# GPIO_5V_LEVEL_SHIFTER.net
KiCad netlist of a schematic drawn in Altium Designer
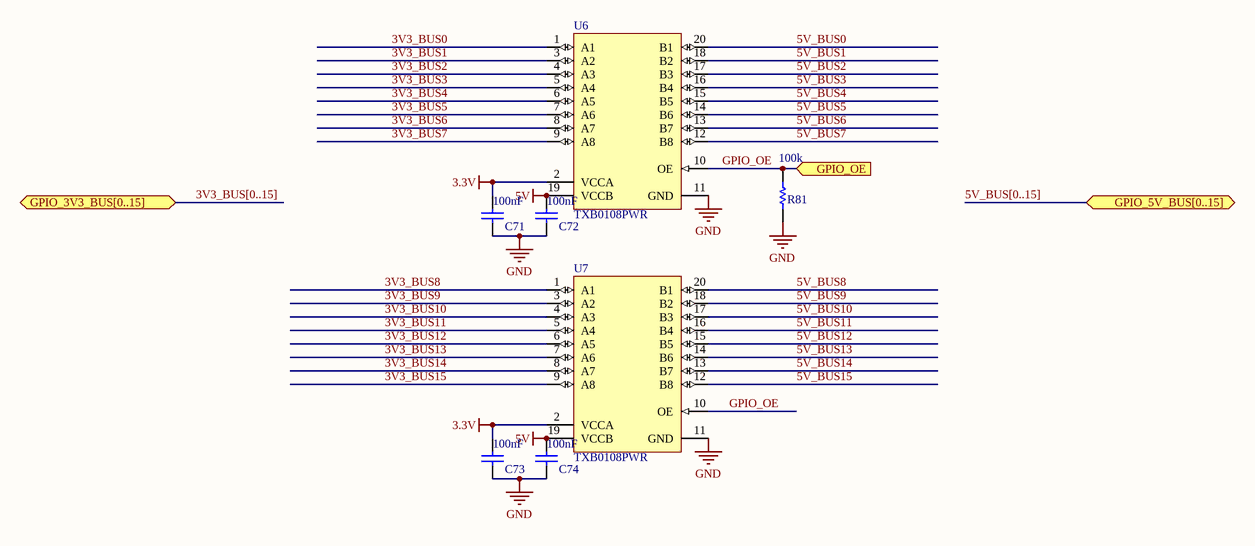
[diagram p0: GPIO_5V_LEVEL_SHIFTER.SchDoc]

(export (version "E")
  (design (tool "Eeschema 10.0.6"))
  (components
    (comp (ref "C71")
      (value "100nF")
      (footprint "CAPC0402(1005)60_L")
      (description "0402 (1005 Metric) Chip Capacitor")
      (fields (field (name "Comment") "CAP0402"))
      (libsource (lib "Altium Content Vault") (part "CMP-1590-00004-1"))
    )
    (comp (ref "C72")
      (value "100nF")
      (footprint "CAPC0402(1005)60_L")
      (description "0402 (1005 Metric) Chip Capacitor")
      (fields (field (name "Comment") "CAP0402"))
      (libsource (lib "Altium Content Vault") (part "CMP-1590-00004-1"))
    )
    (comp (ref "C73")
      (value "100nF")
      (footprint "CAPC0402(1005)60_L")
      (description "0402 (1005 Metric) Chip Capacitor")
      (fields (field (name "Comment") "CAP0402"))
      (libsource (lib "Altium Content Vault") (part "CMP-1590-00004-1"))
    )
    (comp (ref "C74")
      (value "100nF")
      (footprint "CAPC0402(1005)60_L")
      (description "0402 (1005 Metric) Chip Capacitor")
      (fields (field (name "Comment") "CAP0402"))
      (libsource (lib "Altium Content Vault") (part "CMP-1590-00004-1"))
    )
    (comp (ref "R81")
      (value "100k")
      (footprint "RESC0402(1005)_L")
      (description "0402 (1005 Metric) Chip Resistor")
      (fields (field (name "Comment") "RES0402"))
      (libsource (lib "Altium Content Vault") (part "CMP-1591-00004-1"))
    )
    (comp (ref "U6")
      (value "TXB0108PWR")
      (footprint "PW0020A_N")
      (fields (field (name "MANUFACTURER") "Texas Instruments"))
      (libsource (lib "Altium Content Vault") (part "TI-TXB0108-PW-20"))
    )
    (comp (ref "U7")
      (value "TXB0108PWR")
      (footprint "PW0020A_N")
      (fields (field (name "MANUFACTURER") "Texas Instruments"))
      (libsource (lib "Altium Content Vault") (part "TI-TXB0108-PW-20"))
    )
  )
  (nets
    (net (code "1") (name "/3V3_BUS0") (class "Default")
      (node (ref "U6") (pin "1") (pinfunction "A1_1") (pintype "bidirectional"))
    )
    (net (code "2") (name "/3V3_BUS1") (class "Default")
      (node (ref "U6") (pin "3") (pinfunction "A2_3") (pintype "bidirectional"))
    )
    (net (code "3") (name "/3V3_BUS2") (class "Default")
      (node (ref "U6") (pin "4") (pinfunction "A3_4") (pintype "bidirectional"))
    )
    (net (code "4") (name "/3V3_BUS3") (class "Default")
      (node (ref "U6") (pin "5") (pinfunction "A4_5") (pintype "bidirectional"))
    )
    (net (code "5") (name "/3V3_BUS4") (class "Default")
      (node (ref "U6") (pin "6") (pinfunction "A5_6") (pintype "bidirectional"))
    )
    (net (code "6") (name "/3V3_BUS5") (class "Default")
      (node (ref "U6") (pin "7") (pinfunction "A6_7") (pintype "bidirectional"))
    )
    (net (code "7") (name "/3V3_BUS6") (class "Default")
      (node (ref "U6") (pin "8") (pinfunction "A7_8") (pintype "bidirectional"))
    )
    (net (code "8") (name "/3V3_BUS7") (class "Default")
      (node (ref "U6") (pin "9") (pinfunction "A8_9") (pintype "bidirectional"))
    )
    (net (code "9") (name "/3V3_BUS8") (class "Default")
      (node (ref "U7") (pin "1") (pinfunction "A1_1") (pintype "bidirectional"))
    )
    (net (code "10") (name "/3V3_BUS9") (class "Default")
      (node (ref "U7") (pin "3") (pinfunction "A2_3") (pintype "bidirectional"))
    )
    (net (code "11") (name "/3V3_BUS10") (class "Default")
      (node (ref "U7") (pin "4") (pinfunction "A3_4") (pintype "bidirectional"))
    )
    (net (code "12") (name "/3V3_BUS11") (class "Default")
      (node (ref "U7") (pin "5") (pinfunction "A4_5") (pintype "bidirectional"))
    )
    (net (code "13") (name "/3V3_BUS12") (class "Default")
      (node (ref "U7") (pin "6") (pinfunction "A5_6") (pintype "bidirectional"))
    )
    (net (code "14") (name "/3V3_BUS13") (class "Default")
      (node (ref "U7") (pin "7") (pinfunction "A6_7") (pintype "bidirectional"))
    )
    (net (code "15") (name "/3V3_BUS14") (class "Default")
      (node (ref "U7") (pin "8") (pinfunction "A7_8") (pintype "bidirectional"))
    )
    (net (code "16") (name "/3V3_BUS15") (class "Default")
      (node (ref "U7") (pin "9") (pinfunction "A8_9") (pintype "bidirectional"))
    )
    (net (code "18") (name "/5V_BUS0") (class "Default")
      (node (ref "U6") (pin "20") (pinfunction "B1_20") (pintype "bidirectional"))
    )
    (net (code "19") (name "/5V_BUS1") (class "Default")
      (node (ref "U6") (pin "18") (pinfunction "B2_18") (pintype "bidirectional"))
    )
    (net (code "20") (name "/5V_BUS2") (class "Default")
      (node (ref "U6") (pin "17") (pinfunction "B3_17") (pintype "bidirectional"))
    )
    (net (code "21") (name "/5V_BUS3") (class "Default")
      (node (ref "U6") (pin "16") (pinfunction "B4_16") (pintype "bidirectional"))
    )
    (net (code "22") (name "/5V_BUS4") (class "Default")
      (node (ref "U6") (pin "15") (pinfunction "B5_15") (pintype "bidirectional"))
    )
    (net (code "23") (name "/5V_BUS5") (class "Default")
      (node (ref "U6") (pin "14") (pinfunction "B6_14") (pintype "bidirectional"))
    )
    (net (code "24") (name "/5V_BUS6") (class "Default")
      (node (ref "U6") (pin "13") (pinfunction "B7_13") (pintype "bidirectional"))
    )
    (net (code "25") (name "/5V_BUS7") (class "Default")
      (node (ref "U6") (pin "12") (pinfunction "B8_12") (pintype "bidirectional"))
    )
    (net (code "26") (name "/5V_BUS8") (class "Default")
      (node (ref "U7") (pin "20") (pinfunction "B1_20") (pintype "bidirectional"))
    )
    (net (code "27") (name "/5V_BUS9") (class "Default")
      (node (ref "U7") (pin "18") (pinfunction "B2_18") (pintype "bidirectional"))
    )
    (net (code "28") (name "/5V_BUS10") (class "Default")
      (node (ref "U7") (pin "17") (pinfunction "B3_17") (pintype "bidirectional"))
    )
    (net (code "29") (name "/5V_BUS11") (class "Default")
      (node (ref "U7") (pin "16") (pinfunction "B4_16") (pintype "bidirectional"))
    )
    (net (code "30") (name "/5V_BUS12") (class "Default")
      (node (ref "U7") (pin "15") (pinfunction "B5_15") (pintype "bidirectional"))
    )
    (net (code "31") (name "/5V_BUS13") (class "Default")
      (node (ref "U7") (pin "14") (pinfunction "B6_14") (pintype "bidirectional"))
    )
    (net (code "32") (name "/5V_BUS14") (class "Default")
      (node (ref "U7") (pin "13") (pinfunction "B7_13") (pintype "bidirectional"))
    )
    (net (code "33") (name "/5V_BUS15") (class "Default")
      (node (ref "U7") (pin "12") (pinfunction "B8_12") (pintype "bidirectional"))
    )
    (net (code "35") (name "/GPIO_OE") (class "Default")
      (node (ref "R81") (pin "2") (pinfunction "2_2") (pintype "passive"))
      (node (ref "U6") (pin "10") (pinfunction "OE_10") (pintype "input"))
      (node (ref "U7") (pin "10") (pinfunction "OE_10") (pintype "input"))
    )
    (net (code "36") (name "3.3V") (class "Default")
      (node (ref "C71") (pin "1") (pinfunction "1_1") (pintype "passive"))
      (node (ref "C73") (pin "1") (pinfunction "1_1") (pintype "passive"))
      (node (ref "U6") (pin "2") (pinfunction "VCCA_2") (pintype "power_in"))
      (node (ref "U7") (pin "2") (pinfunction "VCCA_2") (pintype "power_in"))
    )
    (net (code "37") (name "5V") (class "Default")
      (node (ref "C72") (pin "1") (pinfunction "1_1") (pintype "passive"))
      (node (ref "C74") (pin "1") (pinfunction "1_1") (pintype "passive"))
      (node (ref "U6") (pin "19") (pinfunction "VCCB_19") (pintype "power_in"))
      (node (ref "U7") (pin "19") (pinfunction "VCCB_19") (pintype "power_in"))
    )
    (net (code "38") (name "GND") (class "Default")
      (node (ref "C71") (pin "2") (pinfunction "2_2") (pintype "passive"))
      (node (ref "C72") (pin "2") (pinfunction "2_2") (pintype "passive"))
      (node (ref "C73") (pin "2") (pinfunction "2_2") (pintype "passive"))
      (node (ref "C74") (pin "2") (pinfunction "2_2") (pintype "passive"))
      (node (ref "R81") (pin "1") (pinfunction "1_1") (pintype "passive"))
      (node (ref "U6") (pin "11") (pinfunction "GND_11") (pintype "power_in"))
      (node (ref "U7") (pin "11") (pinfunction "GND_11") (pintype "power_in"))
    )
  )
)
